# Motor.net
KiCad netlist of a schematic drawn in Altium Designer
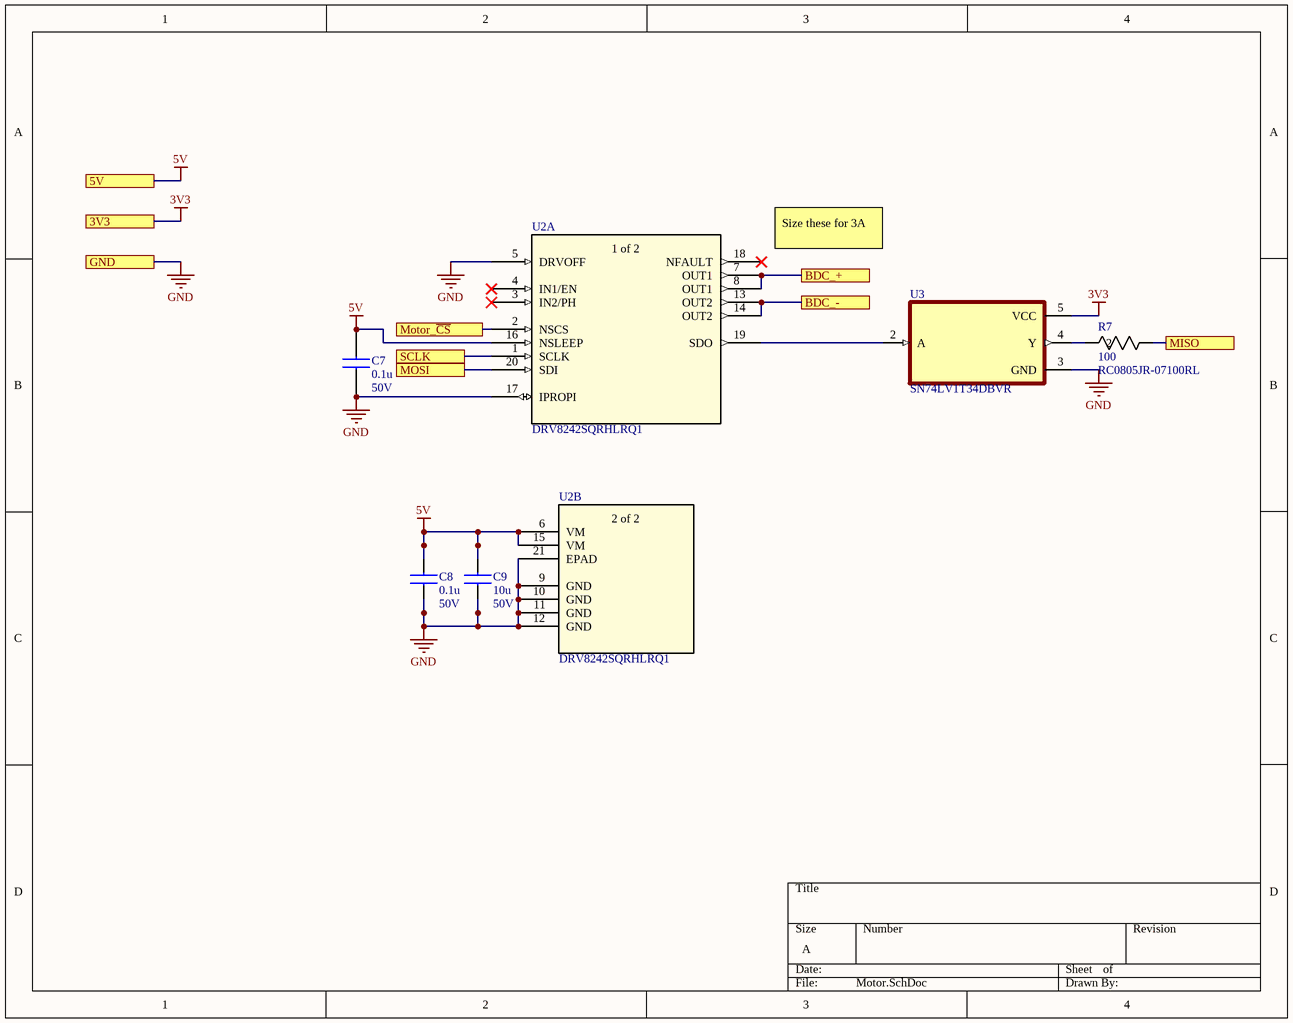
[diagram p0: Motor.SchDoc]

(export (version "E")
  (design (tool "Eeschema 10.0.6"))
  (components
    (comp (ref "C7")
      (value "0.1u")
      (footprint "CAPC2012X145N")
      (description "Multilayer Ceramic Chip Capacitors, Capacitance=0.1u")
      (fields
        (field (name "MANUFACTURER_PART_NUMBER") "KAM21BR71H104JM")
        (field (name "RATED VOLTAGE") "50V")
      )
      (libsource (lib "Caps") (part "KAM21BR71H104JM"))
    )
    (comp (ref "C8")
      (value "0.1u")
      (footprint "CAPC2012X145N")
      (description "Multilayer Ceramic Chip Capacitors, Capacitance=0.1u")
      (fields
        (field (name "MANUFACTURER_PART_NUMBER") "KAM21BR71H104JM")
        (field (name "RATED VOLTAGE") "50V")
      )
      (libsource (lib "Caps") (part "KAM21BR71H104JM"))
    )
    (comp (ref "C9")
      (value "10u")
      (footprint "CAPC2012X145N")
      (description "Multilayer Ceramic Chip Capacitors, Capacitance=10?F, LxWxT:2x1.25x1.25mm")
      (fields
        (field (name "MOUSER PART NUMBER") "810-C2012X5R1H106K12")
        (field (name "MANUFACTURER_PART_NUMBER") "C2012X5R1H106K125AC")
        (field (name "RATED VOLTAGE") "50V")
      )
      (libsource (lib "Caps") (part "C2012X5R1H106K125AC"))
    )
    (comp (ref "R7")
      (value "RC0805JR-07100RL")
      (footprint "RC0805N_YAG")
      (description "RES 0805 100 5% 1/8W")
      (fields (field (name "TOLERANCE") "5%") (field (name "ALTIUM_VALUE") "100"))
      (libsource (lib "Resistors") (part "RC0805JR-07100RL"))
    )
    (comp (ref "U2")
      (value "DRV8242SQRHLRQ1")
      (footprint "VQFN20_RHL_TEX")
      (fields (field (name "COPYRIGHT") "Copyright (C) 2025 Ultra Librarian. All rights reserved."))
      (libsource (lib "DRV8242SQRHLRQ1") (part "DRV8242SQRHLRQ1"))
    )
    (comp (ref "U3")
      (value "SN74LV1T34DBVR")
      (footprint "SOT95P280X145-5N")
      (description "Single Power Supply BUFFER Logic Level Shifter (no enable)")
      (fields (field (name "MF") "Texas Instruments"))
      (libsource (lib "SN74LV1T34DBVR") (part "SN74LV1T34DBVR"))
    )
  )
  (nets
    (net (code "1") (name "/BDC_+") (class "Default")
      (node (ref "U2") (pin "7") (pinfunction "OUT1_7") (pintype "output"))
      (node (ref "U2") (pin "8") (pinfunction "OUT1_8") (pintype "output"))
    )
    (net (code "2") (name "/BDC_-") (class "Default")
      (node (ref "U2") (pin "13") (pinfunction "OUT2_13") (pintype "output"))
      (node (ref "U2") (pin "14") (pinfunction "OUT2_14") (pintype "output"))
    )
    (net (code "3") (name "/MISO") (class "Default")
      (node (ref "R7") (pin "1") (pinfunction "1_1") (pintype "passive"))
    )
    (net (code "4") (name "/MOSI") (class "Default")
      (node (ref "U2") (pin "20") (pinfunction "SDI_20") (pintype "input"))
    )
    (net (code "5") (name "/Motor_~{CS}") (class "Default")
      (node (ref "U2") (pin "2") (pinfunction "NSCS_2") (pintype "input"))
    )
    (net (code "6") (name "/SCLK") (class "Default")
      (node (ref "U2") (pin "1") (pinfunction "SCLK_1") (pintype "input"))
    )
    (net (code "7") (name "3V3") (class "Default")
      (node (ref "U3") (pin "5") (pinfunction "VCC_5") (pintype "power_in"))
    )
    (net (code "8") (name "5V") (class "Default")
      (node (ref "C7") (pin "2") (pinfunction "2_2") (pintype "passive"))
      (node (ref "C8") (pin "2") (pinfunction "2_2") (pintype "passive"))
      (node (ref "C9") (pin "2") (pinfunction "2_2") (pintype "passive"))
      (node (ref "U2") (pin "15") (pinfunction "VM_15") (pintype "power_in"))
      (node (ref "U2") (pin "16") (pinfunction "NSLEEP_16") (pintype "input"))
      (node (ref "U2") (pin "6") (pinfunction "VM_6") (pintype "power_in"))
    )
    (net (code "9") (name "GND") (class "Default")
      (node (ref "C7") (pin "1") (pinfunction "1_1") (pintype "passive"))
      (node (ref "C8") (pin "1") (pinfunction "1_1") (pintype "passive"))
      (node (ref "C9") (pin "1") (pinfunction "1_1") (pintype "passive"))
      (node (ref "U2") (pin "10") (pinfunction "GND_10") (pintype "power_in"))
      (node (ref "U2") (pin "11") (pinfunction "GND_11") (pintype "power_in"))
      (node (ref "U2") (pin "12") (pinfunction "GND_12") (pintype "power_in"))
      (node (ref "U2") (pin "17") (pinfunction "IPROPI_17") (pintype "bidirectional"))
      (node (ref "U2") (pin "21") (pinfunction "EPAD_21") (pintype "power_in"))
      (node (ref "U2") (pin "5") (pinfunction "DRVOFF_5") (pintype "input"))
      (node (ref "U2") (pin "9") (pinfunction "GND_9") (pintype "power_in"))
      (node (ref "U3") (pin "3") (pinfunction "GND_3") (pintype "power_in"))
    )
    (net (code "10") (name "Net-(U2A-SDO)") (class "Default")
      (node (ref "U2") (pin "19") (pinfunction "SDO_19") (pintype "output"))
      (node (ref "U3") (pin "2") (pinfunction "A_2") (pintype "input"))
    )
    (net (code "11") (name "Net-(U3-Y)") (class "Default")
      (node (ref "R7") (pin "2") (pinfunction "2_2") (pintype "passive"))
      (node (ref "U3") (pin "4") (pinfunction "Y_4") (pintype "output"))
    )
    (net (code "12") (name "unconnected-(U2A-IN1{slash}EN-Pad4)") (class "Default")
      (node (ref "U2") (pin "4") (pinfunction "IN1/EN_4") (pintype "input+no_connect"))
    )
    (net (code "13") (name "unconnected-(U2A-IN2{slash}PH-Pad3)") (class "Default")
      (node (ref "U2") (pin "3") (pinfunction "IN2/PH_3") (pintype "input+no_connect"))
    )
    (net (code "14") (name "unconnected-(U2A-NFAULT-Pad18)") (class "Default")
      (node (ref "U2") (pin "18") (pinfunction "NFAULT_18") (pintype "output+no_connect"))
    )
  )
)
